# PX4FMUv2_4_6_09.net
KiCad netlist of a schematic drawn in Altium Designer
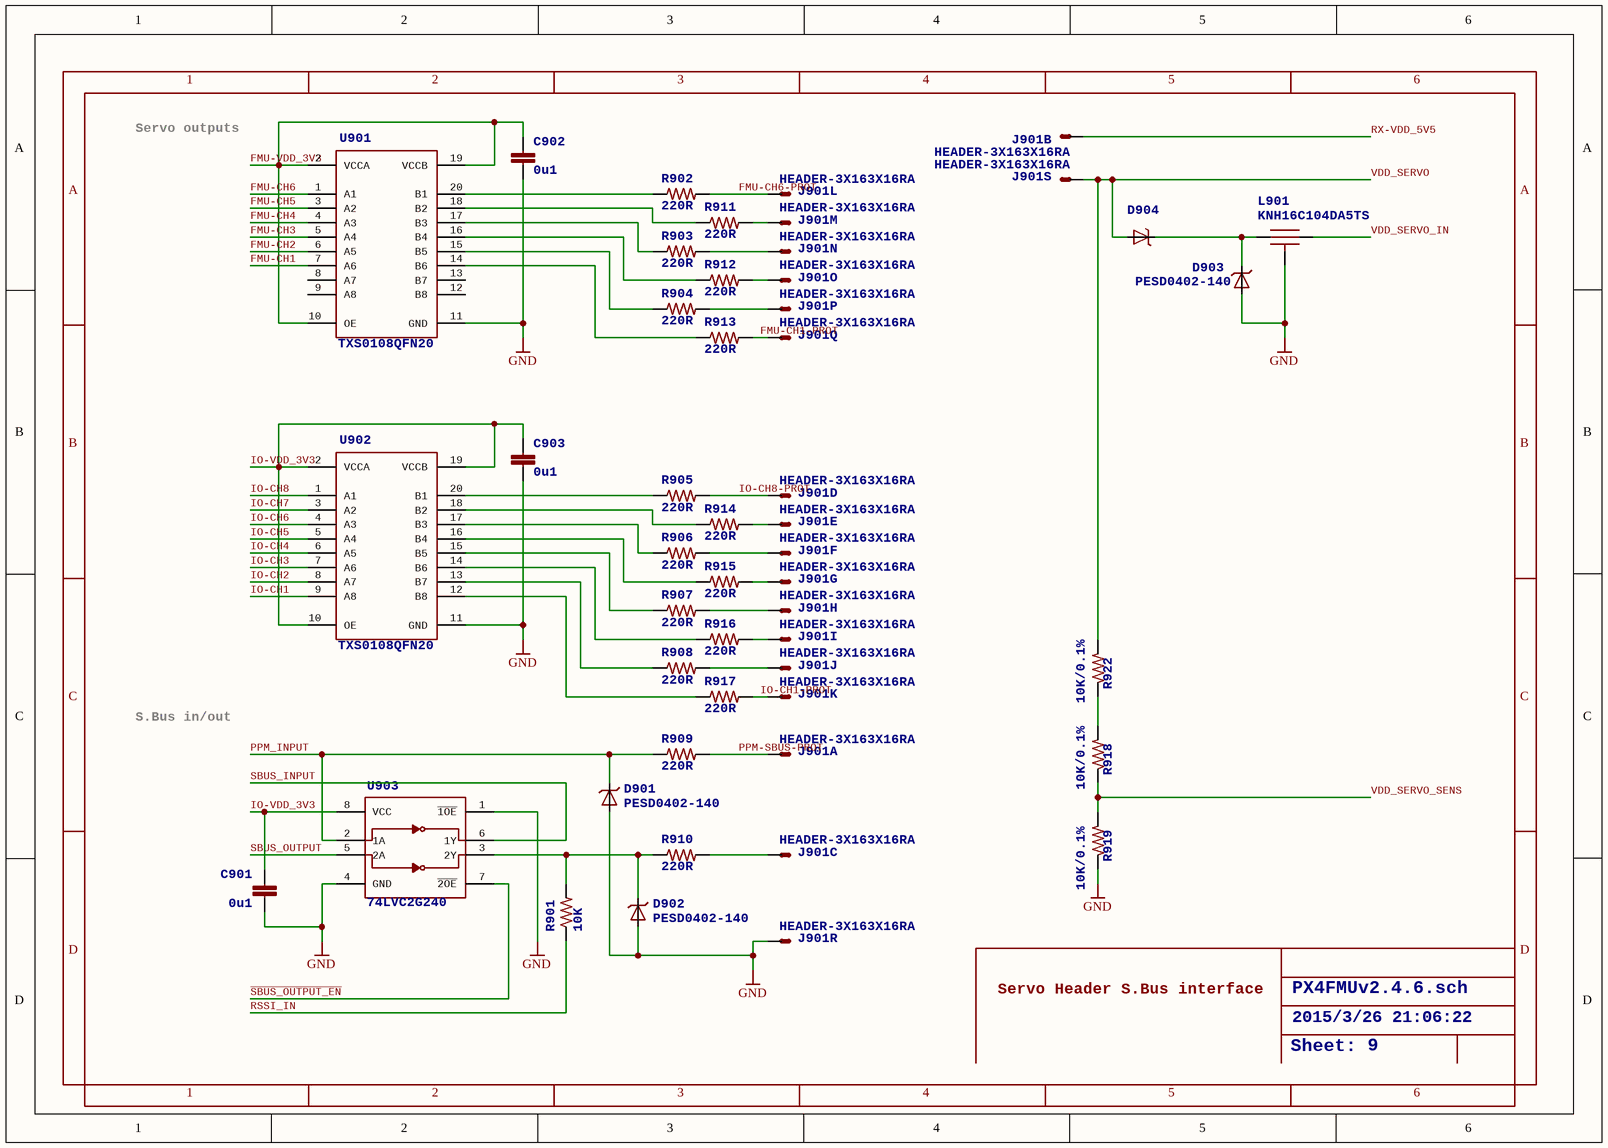
[diagram p0: PX4FMUv2.4.6_09.SchDoc]

(export (version "E")
  (design (tool "Eeschema 10.0.6"))
  (components
    (comp (ref "C901")
      (value "0u1")
      (footprint "0402-CAP")
      (description "<b>Capacitor</b>\nStandard 0603 ceramic capacitor, and 0.1\" leaded capacitor.")
      (fields (field (name "PARTNO") "CC0402ZRY5V7BB104"))
      (libsource (lib "") (part "CAP0402_1"))
    )
    (comp (ref "C902")
      (value "0u1")
      (footprint "0402-CAP")
      (description "<b>Capacitor</b>\nStandard 0603 ceramic capacitor, and 0.1\" leaded capacitor.")
      (fields (field (name "PARTNO") "CC0402ZRY5V7BB104"))
      (libsource (lib "pixhawk2") (part "CAP0402"))
    )
    (comp (ref "C903")
      (value "0u1")
      (footprint "0402-CAP")
      (description "<b>Capacitor</b>\nStandard 0603 ceramic capacitor, and 0.1\" leaded capacitor.")
      (fields (field (name "PARTNO") "CC0402ZRY5V7BB104"))
      (libsource (lib "pixhawk2") (part "CAP0402"))
    )
    (comp (ref "D901")
      (value "PESD0402-140")
      (footprint "0402-TVS")
      (libsource (lib "pixhawk2") (part "DIODE-TVS"))
    )
    (comp (ref "D902")
      (value "PESD0402-140")
      (footprint "0402-TVS")
      (libsource (lib "pixhawk2") (part "DIODE-TVS"))
    )
    (comp (ref "D903")
      (value "PESD0402-140")
      (footprint "0402-TVS")
      (libsource (lib "pixhawk2") (part "DIODE-TVS"))
    )
    (comp (ref "D904")
      (value "MSS1P4-M3")
      (footprint "MICROSMP")
      (description "Schottky barrier diode in DO214AC, e.g. Fairchild SS14.")
      (libsource (lib "pixhawk2") (part "DIODE-SCHOTTKY_MSMP"))
    )
    (comp (ref "J901")
      (value "HEADER-3X163X16RA")
      (footprint "3X16RA")
      (description "3x16 servo header")
      (libsource (lib "pixhawk2") (part "HEADER-3X163X16RA"))
    )
    (comp (ref "L901")
      (value "KNH16C104DA5TS")
      (footprint "KYOCERA-KNH16-DA")
      (description "Kyocera KNH16C104DA5TS EMI filter")
      (libsource (lib "pixhawk2") (part "KNH16C104DA5TS"))
    )
    (comp (ref "R901")
      (value "10K")
      (footprint "0402-RES")
      (fields (field (name "PARTNO") "RC0402FR-0710KL"))
      (libsource (lib "pixhawk2") (part "RESISTOR0402-RES"))
    )
    (comp (ref "R902")
      (value "220R")
      (footprint "0402-RES")
      (fields (field (name "PARTNO") "RC0402FR-07220RL"))
      (libsource (lib "pixhawk2") (part "RESISTOR0402-RES"))
    )
    (comp (ref "R903")
      (value "220R")
      (footprint "0402-RES")
      (fields (field (name "PARTNO") "RC0402FR-07220RL"))
      (libsource (lib "pixhawk2") (part "RESISTOR0402-RES"))
    )
    (comp (ref "R904")
      (value "220R")
      (footprint "0402-RES")
      (fields (field (name "PARTNO") "RC0402FR-07220RL"))
      (libsource (lib "pixhawk2") (part "RESISTOR0402-RES"))
    )
    (comp (ref "R905")
      (value "220R")
      (footprint "0402-RES")
      (fields (field (name "PARTNO") "RC0402FR-07220RL"))
      (libsource (lib "pixhawk2") (part "RESISTOR0402-RES"))
    )
    (comp (ref "R906")
      (value "220R")
      (footprint "0402-RES")
      (fields (field (name "PARTNO") "RC0402FR-07220RL"))
      (libsource (lib "pixhawk2") (part "RESISTOR0402-RES"))
    )
    (comp (ref "R907")
      (value "220R")
      (footprint "0402-RES")
      (fields (field (name "PARTNO") "RC0402FR-07220RL"))
      (libsource (lib "pixhawk2") (part "RESISTOR0402-RES"))
    )
    (comp (ref "R908")
      (value "220R")
      (footprint "0402-RES")
      (fields (field (name "PARTNO") "RC0402FR-07220RL"))
      (libsource (lib "pixhawk2") (part "RESISTOR0402-RES"))
    )
    (comp (ref "R909")
      (value "220R")
      (footprint "0402-RES")
      (fields (field (name "PARTNO") "RC0402FR-07220RL"))
      (libsource (lib "pixhawk2") (part "RESISTOR0402-RES"))
    )
    (comp (ref "R910")
      (value "220R")
      (footprint "0402-RES")
      (fields (field (name "PARTNO") "RC0402FR-07220RL"))
      (libsource (lib "pixhawk2") (part "RESISTOR0402-RES"))
    )
    (comp (ref "R911")
      (value "220R")
      (footprint "0402-RES")
      (fields (field (name "PARTNO") "RC0402FR-07220RL"))
      (libsource (lib "pixhawk2") (part "RESISTOR0402-RES"))
    )
    (comp (ref "R912")
      (value "220R")
      (footprint "0402-RES")
      (fields (field (name "PARTNO") "RC0402FR-07220RL"))
      (libsource (lib "pixhawk2") (part "RESISTOR0402-RES"))
    )
    (comp (ref "R913")
      (value "220R")
      (footprint "0402-RES")
      (fields (field (name "PARTNO") "RC0402FR-07220RL"))
      (libsource (lib "pixhawk2") (part "RESISTOR0402-RES"))
    )
    (comp (ref "R914")
      (value "220R")
      (footprint "0402-RES")
      (fields (field (name "PARTNO") "RC0402FR-07220RL"))
      (libsource (lib "pixhawk2") (part "RESISTOR0402-RES"))
    )
    (comp (ref "R915")
      (value "220R")
      (footprint "0402-RES")
      (fields (field (name "PARTNO") "RC0402FR-07220RL"))
      (libsource (lib "pixhawk2") (part "RESISTOR0402-RES"))
    )
    (comp (ref "R916")
      (value "220R")
      (footprint "0402-RES")
      (fields (field (name "PARTNO") "RC0402FR-07220RL"))
      (libsource (lib "pixhawk2") (part "RESISTOR0402-RES"))
    )
    (comp (ref "R917")
      (value "220R")
      (footprint "0402-RES")
      (fields (field (name "PARTNO") "RC0402FR-07220RL"))
      (libsource (lib "pixhawk2") (part "RESISTOR0402-RES"))
    )
    (comp (ref "R918")
      (value "10K/0.1%")
      (footprint "0402-RES")
      (libsource (lib "pixhawk2") (part "RESISTOR0402-RES"))
    )
    (comp (ref "R919")
      (value "10K/0.1%")
      (footprint "0402-RES")
      (libsource (lib "pixhawk2") (part "RESISTOR0402-RES"))
    )
    (comp (ref "R922")
      (value "10K/0.1%")
      (footprint "0402-RES")
      (libsource (lib "pixhawk2") (part "RESISTOR0402-RES"))
    )
    (comp (ref "U901")
      (value "TXS0108QFN20")
      (footprint "QFN20-RGY")
      (fields (field (name "PARTNO") "TXS0108ERGYR"))
      (libsource (lib "pixhawk2") (part "TXS0108QFN20"))
    )
    (comp (ref "U902")
      (value "TXS0108QFN20")
      (footprint "QFN20-RGY")
      (fields (field (name "PARTNO") "TXS0108ERGYR"))
      (libsource (lib "pixhawk2") (part "TXS0108QFN20"))
    )
    (comp (ref "U903")
      (value "74LVC2G240")
      (footprint "TSSOP8_SOT505-2")
      (fields (field (name "PARTNO") "74LVC2G240DP,125"))
      (libsource (lib "pixhawk2") (part "74LVC2G240-TSSOP-8"))
    )
  )
  (nets
    (net (code "1") (name "/FMU-CH1") (class "Default")
      (node (ref "U901") (pin "7") (pinfunction "A6_7") (pintype "passive"))
    )
    (net (code "2") (name "/FMU-CH1-PROT") (class "Default")
      (node (ref "J901") (pin "46") (pinfunction "S_46") (pintype "passive"))
      (node (ref "R913") (pin "P$2") (pinfunction "2_P$2") (pintype "passive"))
    )
    (net (code "3") (name "/FMU-CH2") (class "Default")
      (node (ref "U901") (pin "6") (pinfunction "A5_6") (pintype "passive"))
    )
    (net (code "4") (name "/FMU-CH3") (class "Default")
      (node (ref "U901") (pin "5") (pinfunction "A4_5") (pintype "passive"))
    )
    (net (code "5") (name "/FMU-CH4") (class "Default")
      (node (ref "U901") (pin "4") (pinfunction "A3_4") (pintype "passive"))
    )
    (net (code "6") (name "/FMU-CH5") (class "Default")
      (node (ref "U901") (pin "3") (pinfunction "A2_3") (pintype "passive"))
    )
    (net (code "7") (name "/FMU-CH6") (class "Default")
      (node (ref "U901") (pin "1") (pinfunction "A1_1") (pintype "passive"))
    )
    (net (code "8") (name "/FMU-CH6-PROT") (class "Default")
      (node (ref "J901") (pin "31") (pinfunction "S_31") (pintype "passive"))
      (node (ref "R902") (pin "P$2") (pinfunction "2_P$2") (pintype "passive"))
    )
    (net (code "9") (name "/FMU-VDD_3V3") (class "Default")
      (node (ref "C902") (pin "P$1") (pinfunction "1_P$1") (pintype "passive"))
      (node (ref "U901") (pin "10") (pinfunction "OE_10") (pintype "passive"))
      (node (ref "U901") (pin "19") (pinfunction "VCCB_19") (pintype "passive"))
      (node (ref "U901") (pin "2") (pinfunction "VCCA_2") (pintype "passive"))
    )
    (net (code "10") (name "/IO-CH1") (class "Default")
      (node (ref "U902") (pin "9") (pinfunction "A8_9") (pintype "passive"))
    )
    (net (code "11") (name "/IO-CH1-PROT") (class "Default")
      (node (ref "J901") (pin "28") (pinfunction "S_28") (pintype "passive"))
      (node (ref "R917") (pin "P$2") (pinfunction "2_P$2") (pintype "passive"))
    )
    (net (code "12") (name "/IO-CH2") (class "Default")
      (node (ref "U902") (pin "8") (pinfunction "A7_8") (pintype "passive"))
    )
    (net (code "13") (name "/IO-CH3") (class "Default")
      (node (ref "U902") (pin "7") (pinfunction "A6_7") (pintype "passive"))
    )
    (net (code "14") (name "/IO-CH4") (class "Default")
      (node (ref "U902") (pin "6") (pinfunction "A5_6") (pintype "passive"))
    )
    (net (code "15") (name "/IO-CH5") (class "Default")
      (node (ref "U902") (pin "5") (pinfunction "A4_5") (pintype "passive"))
    )
    (net (code "16") (name "/IO-CH6") (class "Default")
      (node (ref "U902") (pin "4") (pinfunction "A3_4") (pintype "passive"))
    )
    (net (code "17") (name "/IO-CH7") (class "Default")
      (node (ref "U902") (pin "3") (pinfunction "A2_3") (pintype "passive"))
    )
    (net (code "18") (name "/IO-CH8") (class "Default")
      (node (ref "U902") (pin "1") (pinfunction "A1_1") (pintype "passive"))
    )
    (net (code "19") (name "/IO-CH8-PROT") (class "Default")
      (node (ref "J901") (pin "7") (pinfunction "S_7") (pintype "passive"))
      (node (ref "R905") (pin "P$2") (pinfunction "2_P$2") (pintype "passive"))
    )
    (net (code "20") (name "/IO-VDD_3V3") (class "Default")
      (node (ref "C901") (pin "P$1") (pinfunction "1_P$1") (pintype "passive"))
      (node (ref "C903") (pin "P$1") (pinfunction "1_P$1") (pintype "passive"))
      (node (ref "U902") (pin "10") (pinfunction "OE_10") (pintype "passive"))
      (node (ref "U902") (pin "19") (pinfunction "VCCB_19") (pintype "passive"))
      (node (ref "U902") (pin "2") (pinfunction "VCCA_2") (pintype "passive"))
      (node (ref "U903") (pin "8") (pinfunction "VCC_8") (pintype "open_emitter"))
    )
    (net (code "21") (name "/PPM-SBUS-PROT") (class "Default")
      (node (ref "J901") (pin "1") (pinfunction "S_1") (pintype "passive"))
      (node (ref "R909") (pin "P$2") (pinfunction "2_P$2") (pintype "passive"))
    )
    (net (code "22") (name "/PPM_INPUT") (class "Default")
      (node (ref "D901") (pin "C") (pinfunction "C_C") (pintype "passive"))
      (node (ref "R909") (pin "P$1") (pinfunction "1_P$1") (pintype "passive"))
      (node (ref "U903") (pin "2") (pinfunction "1A_2") (pintype "passive"))
    )
    (net (code "23") (name "/RSSI_IN") (class "Default")
      (node (ref "R901") (pin "P$1") (pinfunction "1_P$1") (pintype "passive"))
    )
    (net (code "24") (name "/RX-VDD_5V5") (class "Default")
      (node (ref "J901") (pin "2") (pinfunction "S_2") (pintype "passive"))
    )
    (net (code "25") (name "/SBUS_INPUT") (class "Default")
      (node (ref "U903") (pin "6") (pinfunction "1Y_6") (pintype "passive"))
    )
    (net (code "26") (name "/SBUS_OUTPUT") (class "Default")
      (node (ref "U903") (pin "5") (pinfunction "2A_5") (pintype "passive"))
    )
    (net (code "27") (name "/VDD_SERVO") (class "Default")
      (node (ref "D904") (pin "ANODE") (pinfunction "A_ANODE") (pintype "passive"))
      (node (ref "J901") (pin "5_8_11_14_17_20_23_26_29_32_35_38_41_44_47") (pinfunction "S_5_8_11_14_17_20_23_26_29_32_35_38_41_44_47") (pintype "passive"))
      (node (ref "R922") (pin "P$2") (pinfunction "2_P$2") (pintype "passive"))
    )
    (net (code "28") (name "/VDD_SERVO_IN") (class "Default")
      (node (ref "L901") (pin "P$2") (pinfunction "P$2_P$2") (pintype "passive"))
    )
    (net (code "29") (name "/VDD_SERVO_SENS") (class "Default")
      (node (ref "R918") (pin "P$1") (pinfunction "1_P$1") (pintype "passive"))
      (node (ref "R919") (pin "P$2") (pinfunction "2_P$2") (pintype "passive"))
    )
    (net (code "30") (name "/~{SBUS_OUTPUT_EN}") (class "Default")
      (node (ref "U903") (pin "7") (pinfunction "~{2OE}_7") (pintype "passive"))
    )
    (net (code "31") (name "GND") (class "Default")
      (node (ref "C901") (pin "P$2") (pinfunction "2_P$2") (pintype "passive"))
      (node (ref "C902") (pin "P$2") (pinfunction "2_P$2") (pintype "passive"))
      (node (ref "C903") (pin "P$2") (pinfunction "2_P$2") (pintype "passive"))
      (node (ref "D901") (pin "A") (pinfunction "A_A") (pintype "passive"))
      (node (ref "D902") (pin "A") (pinfunction "A_A") (pintype "passive"))
      (node (ref "D903") (pin "A") (pinfunction "A_A") (pintype "passive"))
      (node (ref "J901") (pin "3_6_9_12_15_18_21_24_27_30_33_36_39_42_45_48") (pinfunction "S_3_6_9_12_15_18_21_24_27_30_33_36_39_42_45_48") (pintype "passive"))
      (node (ref "L901") (pin "P$3_P$4_P$5") (pinfunction "P$3_P$3_P$4_P$5") (pintype "passive"))
      (node (ref "R919") (pin "P$1") (pinfunction "1_P$1") (pintype "passive"))
      (node (ref "U901") (pin "11") (pinfunction "GND_11") (pintype "open_emitter"))
      (node (ref "U902") (pin "11") (pinfunction "GND_11") (pintype "open_emitter"))
      (node (ref "U903") (pin "1") (pinfunction "~{1OE}_1") (pintype "passive"))
      (node (ref "U903") (pin "4") (pinfunction "GND_4") (pintype "open_emitter"))
    )
    (net (code "32") (name "Net-(D904-C)") (class "Default")
      (node (ref "D903") (pin "C") (pinfunction "C_C") (pintype "passive"))
      (node (ref "D904") (pin "CATHODE") (pinfunction "C_CATHODE") (pintype "passive"))
      (node (ref "L901") (pin "P$1") (pinfunction "P$1_P$1") (pintype "passive"))
    )
    (net (code "33") (name "Net-(J901C-S)") (class "Default")
      (node (ref "J901") (pin "4") (pinfunction "S_4") (pintype "passive"))
      (node (ref "R910") (pin "P$2") (pinfunction "2_P$2") (pintype "passive"))
    )
    (net (code "34") (name "Net-(J901E-S)") (class "Default")
      (node (ref "J901") (pin "10") (pinfunction "S_10") (pintype "passive"))
      (node (ref "R914") (pin "P$2") (pinfunction "2_P$2") (pintype "passive"))
    )
    (net (code "35") (name "Net-(J901F-S)") (class "Default")
      (node (ref "J901") (pin "13") (pinfunction "S_13") (pintype "passive"))
      (node (ref "R906") (pin "P$2") (pinfunction "2_P$2") (pintype "passive"))
    )
    (net (code "36") (name "Net-(J901G-S)") (class "Default")
      (node (ref "J901") (pin "16") (pinfunction "S_16") (pintype "passive"))
      (node (ref "R915") (pin "P$2") (pinfunction "2_P$2") (pintype "passive"))
    )
    (net (code "37") (name "Net-(J901H-S)") (class "Default")
      (node (ref "J901") (pin "19") (pinfunction "S_19") (pintype "passive"))
      (node (ref "R907") (pin "P$2") (pinfunction "2_P$2") (pintype "passive"))
    )
    (net (code "38") (name "Net-(J901I-S)") (class "Default")
      (node (ref "J901") (pin "22") (pinfunction "S_22") (pintype "passive"))
      (node (ref "R916") (pin "P$2") (pinfunction "2_P$2") (pintype "passive"))
    )
    (net (code "39") (name "Net-(J901J-S)") (class "Default")
      (node (ref "J901") (pin "25") (pinfunction "S_25") (pintype "passive"))
      (node (ref "R908") (pin "P$2") (pinfunction "2_P$2") (pintype "passive"))
    )
    (net (code "40") (name "Net-(J901M-S)") (class "Default")
      (node (ref "J901") (pin "34") (pinfunction "S_34") (pintype "passive"))
      (node (ref "R911") (pin "P$2") (pinfunction "2_P$2") (pintype "passive"))
    )
    (net (code "41") (name "Net-(J901N-S)") (class "Default")
      (node (ref "J901") (pin "37") (pinfunction "S_37") (pintype "passive"))
      (node (ref "R903") (pin "P$2") (pinfunction "2_P$2") (pintype "passive"))
    )
    (net (code "42") (name "Net-(J901O-S)") (class "Default")
      (node (ref "J901") (pin "40") (pinfunction "S_40") (pintype "passive"))
      (node (ref "R912") (pin "P$2") (pinfunction "2_P$2") (pintype "passive"))
    )
    (net (code "43") (name "Net-(J901P-S)") (class "Default")
      (node (ref "J901") (pin "43") (pinfunction "S_43") (pintype "passive"))
      (node (ref "R904") (pin "P$2") (pinfunction "2_P$2") (pintype "passive"))
    )
    (net (code "44") (name "Net-(R901-2)") (class "Default")
      (node (ref "D902") (pin "C") (pinfunction "C_C") (pintype "passive"))
      (node (ref "R901") (pin "P$2") (pinfunction "2_P$2") (pintype "passive"))
      (node (ref "R910") (pin "P$1") (pinfunction "1_P$1") (pintype "passive"))
      (node (ref "U903") (pin "3") (pinfunction "2Y_3") (pintype "passive"))
    )
    (net (code "45") (name "Net-(R902-1)") (class "Default")
      (node (ref "R902") (pin "P$1") (pinfunction "1_P$1") (pintype "passive"))
      (node (ref "U901") (pin "20") (pinfunction "B1_20") (pintype "passive"))
    )
    (net (code "46") (name "Net-(R903-1)") (class "Default")
      (node (ref "R903") (pin "P$1") (pinfunction "1_P$1") (pintype "passive"))
      (node (ref "U901") (pin "17") (pinfunction "B3_17") (pintype "passive"))
    )
    (net (code "47") (name "Net-(R904-1)") (class "Default")
      (node (ref "R904") (pin "P$1") (pinfunction "1_P$1") (pintype "passive"))
      (node (ref "U901") (pin "15") (pinfunction "B5_15") (pintype "passive"))
    )
    (net (code "48") (name "Net-(R905-1)") (class "Default")
      (node (ref "R905") (pin "P$1") (pinfunction "1_P$1") (pintype "passive"))
      (node (ref "U902") (pin "20") (pinfunction "B1_20") (pintype "passive"))
    )
    (net (code "49") (name "Net-(R906-1)") (class "Default")
      (node (ref "R906") (pin "P$1") (pinfunction "1_P$1") (pintype "passive"))
      (node (ref "U902") (pin "17") (pinfunction "B3_17") (pintype "passive"))
    )
    (net (code "50") (name "Net-(R907-1)") (class "Default")
      (node (ref "R907") (pin "P$1") (pinfunction "1_P$1") (pintype "passive"))
      (node (ref "U902") (pin "15") (pinfunction "B5_15") (pintype "passive"))
    )
    (net (code "51") (name "Net-(R908-1)") (class "Default")
      (node (ref "R908") (pin "P$1") (pinfunction "1_P$1") (pintype "passive"))
      (node (ref "U902") (pin "13") (pinfunction "B7_13") (pintype "passive"))
    )
    (net (code "52") (name "Net-(R911-1)") (class "Default")
      (node (ref "R911") (pin "P$1") (pinfunction "1_P$1") (pintype "passive"))
      (node (ref "U901") (pin "18") (pinfunction "B2_18") (pintype "passive"))
    )
    (net (code "53") (name "Net-(R912-1)") (class "Default")
      (node (ref "R912") (pin "P$1") (pinfunction "1_P$1") (pintype "passive"))
      (node (ref "U901") (pin "16") (pinfunction "B4_16") (pintype "passive"))
    )
    (net (code "54") (name "Net-(R913-1)") (class "Default")
      (node (ref "R913") (pin "P$1") (pinfunction "1_P$1") (pintype "passive"))
      (node (ref "U901") (pin "14") (pinfunction "B6_14") (pintype "passive"))
    )
    (net (code "55") (name "Net-(R914-1)") (class "Default")
      (node (ref "R914") (pin "P$1") (pinfunction "1_P$1") (pintype "passive"))
      (node (ref "U902") (pin "18") (pinfunction "B2_18") (pintype "passive"))
    )
    (net (code "56") (name "Net-(R915-1)") (class "Default")
      (node (ref "R915") (pin "P$1") (pinfunction "1_P$1") (pintype "passive"))
      (node (ref "U902") (pin "16") (pinfunction "B4_16") (pintype "passive"))
    )
    (net (code "57") (name "Net-(R916-1)") (class "Default")
      (node (ref "R916") (pin "P$1") (pinfunction "1_P$1") (pintype "passive"))
      (node (ref "U902") (pin "14") (pinfunction "B6_14") (pintype "passive"))
    )
    (net (code "58") (name "Net-(R917-1)") (class "Default")
      (node (ref "R917") (pin "P$1") (pinfunction "1_P$1") (pintype "passive"))
      (node (ref "U902") (pin "12") (pinfunction "B8_12") (pintype "passive"))
    )
    (net (code "59") (name "Net-(R918-2)") (class "Default")
      (node (ref "R918") (pin "P$2") (pinfunction "2_P$2") (pintype "passive"))
      (node (ref "R922") (pin "P$1") (pinfunction "1_P$1") (pintype "passive"))
    )
    (net (code "60") (name "unconnected-(U901-A7-Pad8)") (class "Default")
      (node (ref "U901") (pin "8") (pinfunction "A7_8") (pintype "passive"))
    )
    (net (code "61") (name "unconnected-(U901-A8-Pad9)") (class "Default")
      (node (ref "U901") (pin "9") (pinfunction "A8_9") (pintype "passive"))
    )
    (net (code "62") (name "unconnected-(U901-B7-Pad13)") (class "Default")
      (node (ref "U901") (pin "13") (pinfunction "B7_13") (pintype "passive"))
    )
    (net (code "63") (name "unconnected-(U901-B8-Pad12)") (class "Default")
      (node (ref "U901") (pin "12") (pinfunction "B8_12") (pintype "passive"))
    )
  )
)
